# main.net
KiCad netlist of a schematic drawn in EAGLE
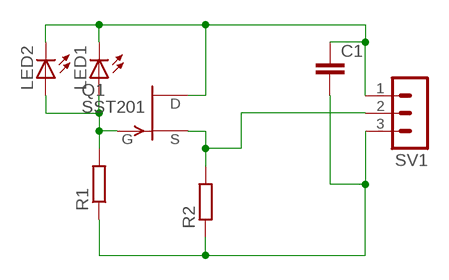
[diagram p0: schematic, sheet 1]

(export (version "E")
  (design (tool "Eeschema 10.0.6"))
  (components
    (comp (ref "C1")
      (value "C-EU025-050X050")
      (footprint "eagle-import:C025-050X050")
      (libsource (lib "eagle-import") (part "C-EU025-050X050"))
    )
    (comp (ref "LED1")
      (value "LEDSFH480")
      (footprint "eagle-import:SFH480")
      (libsource (lib "eagle-import") (part "LEDSFH480"))
    )
    (comp (ref "LED2")
      (value "LEDSFH480")
      (footprint "eagle-import:SFH480")
      (libsource (lib "eagle-import") (part "LEDSFH480"))
    )
    (comp (ref "Q1")
      (value "SST201")
      (footprint "eagle-import:SOT23")
      (libsource (lib "eagle-import") (part "?20SST1"))
    )
    (comp (ref "R1")
      (value "R-EU_0204/7")
      (footprint "eagle-import:0204_7")
      (libsource (lib "eagle-import") (part "R-EU_0204/7"))
    )
    (comp (ref "R2")
      (value "R-EU_0204/7")
      (footprint "eagle-import:0204_7")
      (libsource (lib "eagle-import") (part "R-EU_0204/7"))
    )
    (comp (ref "SV1")
      (value "MA03-1")
      (footprint "eagle-import:MA03-1")
      (libsource (lib "eagle-import") (part "MA03-1"))
    )
  )
  (nets
    (net (code "1") (name "Net-(C1-Pad2)") (class "Default")
      (node (ref "C1") (pin "2") (pinfunction "2_2") (pintype "passive"))
      (node (ref "R1") (pin "1") (pinfunction "1_1") (pintype "passive"))
      (node (ref "R2") (pin "1") (pinfunction "1_1") (pintype "passive"))
      (node (ref "SV1") (pin "3") (pinfunction "3_3") (pintype "passive"))
    )
    (net (code "2") (name "Net-(LED1-C)") (class "Default")
      (node (ref "C1") (pin "1") (pinfunction "1_1") (pintype "passive"))
      (node (ref "LED1") (pin "K") (pinfunction "C_K") (pintype "passive"))
      (node (ref "LED2") (pin "K") (pinfunction "C_K") (pintype "passive"))
      (node (ref "Q1") (pin "1") (pinfunction "D_1") (pintype "passive"))
      (node (ref "SV1") (pin "1") (pinfunction "1_1") (pintype "passive"))
    )
    (net (code "3") (name "Net-(Q1-G)") (class "Default")
      (node (ref "LED1") (pin "A") (pinfunction "A_A") (pintype "passive"))
      (node (ref "LED2") (pin "A") (pinfunction "A_A") (pintype "passive"))
      (node (ref "Q1") (pin "3") (pinfunction "G_3") (pintype "passive"))
      (node (ref "R1") (pin "2") (pinfunction "2_2") (pintype "passive"))
    )
    (net (code "4") (name "Net-(Q1-S)") (class "Default")
      (node (ref "Q1") (pin "2") (pinfunction "S_2") (pintype "passive"))
      (node (ref "R2") (pin "2") (pinfunction "2_2") (pintype "passive"))
      (node (ref "SV1") (pin "2") (pinfunction "2_2") (pintype "passive"))
    )
  )
)
